# unicycle_v2_3.net
KiCad netlist of a schematic drawn in EAGLE
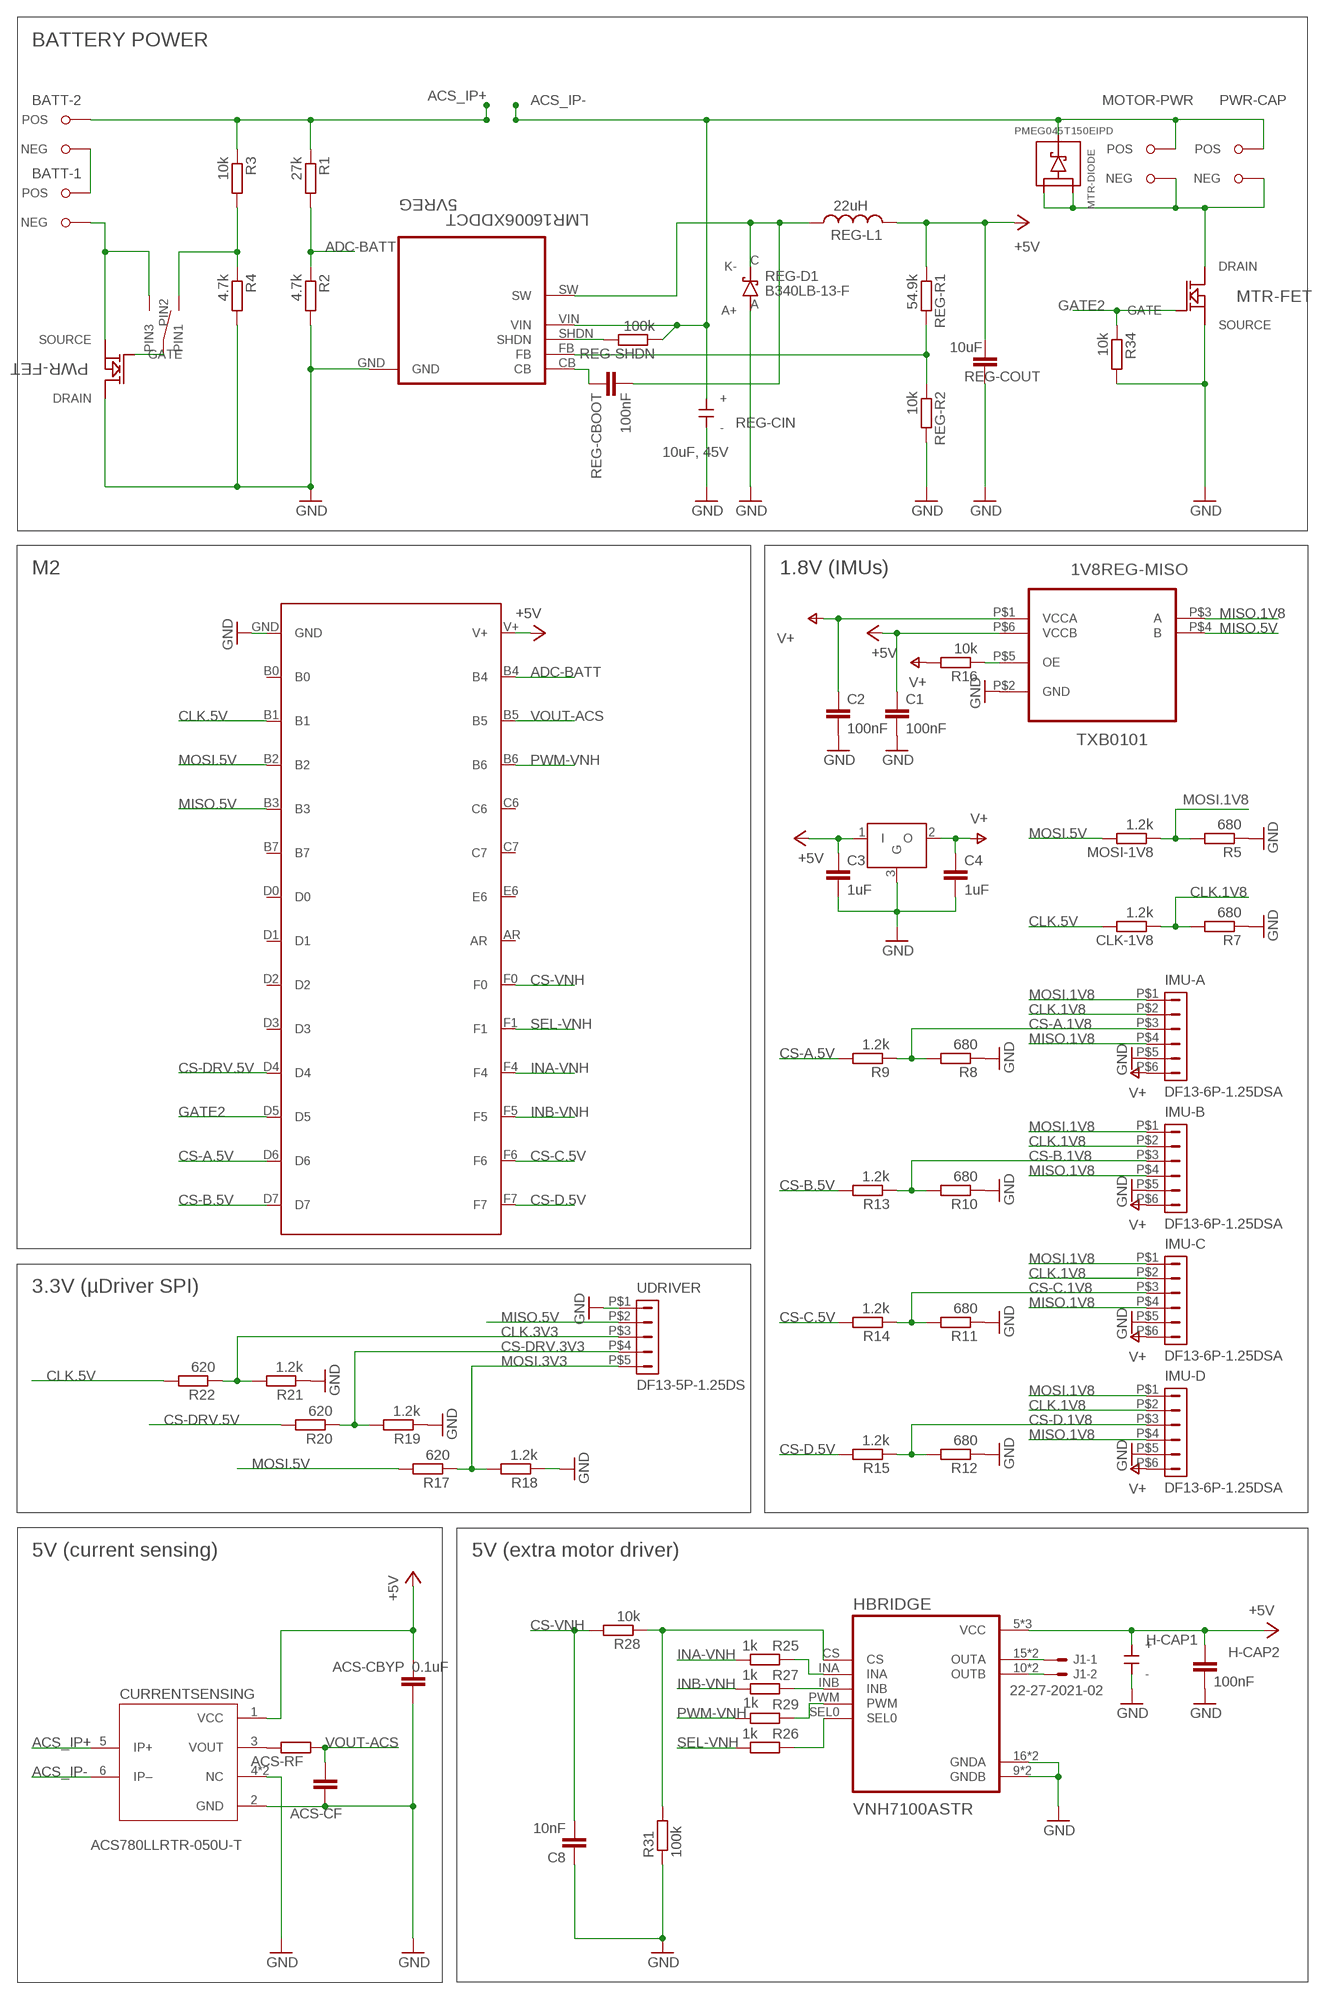
[diagram p0: schematic, sheet 1]

(export (version "E")
  (design (tool "Eeschema 10.0.6"))
  (components
    (comp (ref "1V8-REG")
      (value "AP7333AG")
      (footprint "eagle-import:SOT23")
      (libsource (lib "eagle-import") (part "AP7333AG"))
    )
    (comp (ref "1V8REG-MISO")
      (value "TXB0101")
      (footprint "eagle-import:SOT23-6")
      (libsource (lib "eagle-import") (part "TXB0101"))
    )
    (comp (ref "5VREG")
      (value "LMR16006XDDCT")
      (footprint "eagle-import:SOT95P280X110-6N")
      (fields (field (name "MF") "Texas Instruments"))
      (libsource (lib "eagle-import") (part "LMR16006XDDCT"))
    )
    (comp (ref "ACS-CBYP")
      (value "0.1uF")
      (footprint "eagle-import:C0603")
      (libsource (lib "eagle-import") (part "C-EUC0603"))
    )
    (comp (ref "ACS-CF")
      (value "C-EUC0603")
      (footprint "eagle-import:C0603")
      (libsource (lib "eagle-import") (part "C-EUC0603"))
    )
    (comp (ref "ACS-RF")
      (value "R-EU_R0603")
      (footprint "eagle-import:R0603")
      (libsource (lib "eagle-import") (part "R-EU_R0603"))
    )
    (comp (ref "C1")
      (value "100nF")
      (footprint "eagle-import:C0402")
      (libsource (lib "eagle-import") (part "zz-jpf_C-EUC0402"))
    )
    (comp (ref "C2")
      (value "100nF")
      (footprint "eagle-import:C0402")
      (libsource (lib "eagle-import") (part "zz-jpf_C-EUC0402"))
    )
    (comp (ref "C3")
      (value "1uF")
      (footprint "eagle-import:C0402")
      (libsource (lib "eagle-import") (part "zz-jpf_C-EUC0402"))
    )
    (comp (ref "C4")
      (value "1uF")
      (footprint "eagle-import:C0402")
      (libsource (lib "eagle-import") (part "zz-jpf_C-EUC0402"))
    )
    (comp (ref "C8")
      (value "10nF")
      (footprint "eagle-import:C0402")
      (libsource (lib "eagle-import") (part "zz-jpf_C-EUC0402"))
    )
    (comp (ref "CLK-1V8")
      (value "1.2k")
      (footprint "eagle-import:R0402")
      (libsource (lib "eagle-import") (part "zz-jpf_R-EU_R0402"))
    )
    (comp (ref "CURRENTSENSING")
      (value "ACS780LLRTR-050U-T")
      (footprint "eagle-import:XDCR_ACS780LLRTR-050B-T")
      (fields (field (name "MF") "Allegro MicroSystems LLC"))
      (libsource (lib "eagle-import") (part "ACS780LLRTR-050U-T"))
    )
    (comp (ref "H-CAP1")
      (value "TPSD337K006R0045")
      (footprint "eagle-import:AVX_TPS-D")
      (fields (field (name "MF") "AVX Corporation"))
      (libsource (lib "eagle-import") (part "TPSD337K006R0045"))
    )
    (comp (ref "H-CAP2")
      (value "100nF")
      (footprint "eagle-import:C0402")
      (libsource (lib "eagle-import") (part "zz-jpf_C-EUC0402"))
    )
    (comp (ref "HBRIDGE")
      (value "VNH7100ASTR")
      (footprint "eagle-import:SOIC127P600X175-16N")
      (fields (field (name "MF") "STMicroelectronics"))
      (libsource (lib "eagle-import") (part "VNH7100ASTR"))
    )
    (comp (ref "IMU-A")
      (value "DF13-6P-1.25DSA")
      (footprint "eagle-import:DF13-6P-1.25DSA")
      (libsource (lib "eagle-import") (part "DF13-6P-1.25DSA"))
    )
    (comp (ref "IMU-B")
      (value "DF13-6P-1.25DSA")
      (footprint "eagle-import:DF13-6P-1.25DSA")
      (libsource (lib "eagle-import") (part "DF13-6P-1.25DSA"))
    )
    (comp (ref "IMU-C")
      (value "DF13-6P-1.25DSA")
      (footprint "eagle-import:DF13-6P-1.25DSA")
      (libsource (lib "eagle-import") (part "DF13-6P-1.25DSA"))
    )
    (comp (ref "IMU-D")
      (value "DF13-6P-1.25DSA")
      (footprint "eagle-import:DF13-6P-1.25DSA")
      (libsource (lib "eagle-import") (part "DF13-6P-1.25DSA"))
    )
    (comp (ref "J1")
      (value "22-27-2021-02")
      (footprint "eagle-import:6410-02")
      (fields (field (name "MF") "MOLEX"))
      (libsource (lib "eagle-import") (part "22-?-0227-2021"))
    )
    (comp (ref "MOSI-1V8")
      (value "1.2k")
      (footprint "eagle-import:R0402")
      (libsource (lib "eagle-import") (part "zz-jpf_R-EU_R0402"))
    )
    (comp (ref "MOTOR-PWR")
      (value "21AWG_X2")
      (footprint "eagle-import:21AWG_X2")
      (libsource (lib "eagle-import") (part "21AWG_X2"))
    )
    (comp (ref "MTR-DIODE")
      (value "PMEG045T150EIPD")
      (footprint "eagle-import:PMEG045T150EIPD")
      (fields (field (name "MF") "Nexperia USA Inc."))
      (libsource (lib "eagle-import") (part "PMEG045T150EIPD"))
    )
    (comp (ref "MTR-FET")
      (value "CSD18540Q5BT")
      (footprint "eagle-import:DNK0008A")
      (fields (field (name "MF") "Texas Instruments"))
      (libsource (lib "eagle-import") (part "CSD18540Q5BT"))
    )
    (comp (ref "PWR-CAP")
      (value "21AWG_X2")
      (footprint "eagle-import:21AWG_X2")
      (libsource (lib "eagle-import") (part "21AWG_X2"))
    )
    (comp (ref "PWR-FET")
      (value "CSD18540Q5BT")
      (footprint "eagle-import:DNK0008A")
      (fields (field (name "MF") "Texas Instruments"))
      (libsource (lib "eagle-import") (part "CSD18540Q5BT"))
    )
    (comp (ref "R1")
      (value "27k")
      (footprint "eagle-import:R0402")
      (libsource (lib "eagle-import") (part "zz-jpf_R-EU_R0402"))
    )
    (comp (ref "R2")
      (value "4.7k")
      (footprint "eagle-import:R0402")
      (libsource (lib "eagle-import") (part "zz-jpf_R-EU_R0402"))
    )
    (comp (ref "R3")
      (value "10k")
      (footprint "eagle-import:R0402")
      (libsource (lib "eagle-import") (part "zz-jpf_R-EU_R0402"))
    )
    (comp (ref "R4")
      (value "4.7k")
      (footprint "eagle-import:R0402")
      (libsource (lib "eagle-import") (part "zz-jpf_R-EU_R0402"))
    )
    (comp (ref "R5")
      (value "680")
      (footprint "eagle-import:R0402")
      (libsource (lib "eagle-import") (part "zz-jpf_R-EU_R0402"))
    )
    (comp (ref "R7")
      (value "680")
      (footprint "eagle-import:R0402")
      (libsource (lib "eagle-import") (part "zz-jpf_R-EU_R0402"))
    )
    (comp (ref "R8")
      (value "680")
      (footprint "eagle-import:R0402")
      (libsource (lib "eagle-import") (part "zz-jpf_R-EU_R0402"))
    )
    (comp (ref "R9")
      (value "1.2k")
      (footprint "eagle-import:R0402")
      (libsource (lib "eagle-import") (part "zz-jpf_R-EU_R0402"))
    )
    (comp (ref "R10")
      (value "680")
      (footprint "eagle-import:R0402")
      (libsource (lib "eagle-import") (part "zz-jpf_R-EU_R0402"))
    )
    (comp (ref "R11")
      (value "680")
      (footprint "eagle-import:R0402")
      (libsource (lib "eagle-import") (part "zz-jpf_R-EU_R0402"))
    )
    (comp (ref "R12")
      (value "680")
      (footprint "eagle-import:R0402")
      (libsource (lib "eagle-import") (part "zz-jpf_R-EU_R0402"))
    )
    (comp (ref "R13")
      (value "1.2k")
      (footprint "eagle-import:R0402")
      (libsource (lib "eagle-import") (part "zz-jpf_R-EU_R0402"))
    )
    (comp (ref "R14")
      (value "1.2k")
      (footprint "eagle-import:R0402")
      (libsource (lib "eagle-import") (part "zz-jpf_R-EU_R0402"))
    )
    (comp (ref "R15")
      (value "1.2k")
      (footprint "eagle-import:R0402")
      (libsource (lib "eagle-import") (part "zz-jpf_R-EU_R0402"))
    )
    (comp (ref "R16")
      (value "10k")
      (footprint "eagle-import:R0402")
      (libsource (lib "eagle-import") (part "zz-jpf_R-EU_R0402"))
    )
    (comp (ref "R17")
      (value "620")
      (footprint "eagle-import:R0402")
      (libsource (lib "eagle-import") (part "zz-jpf_R-EU_R0402"))
    )
    (comp (ref "R18")
      (value "1.2k")
      (footprint "eagle-import:R0402")
      (libsource (lib "eagle-import") (part "zz-jpf_R-EU_R0402"))
    )
    (comp (ref "R19")
      (value "1.2k")
      (footprint "eagle-import:R0402")
      (libsource (lib "eagle-import") (part "zz-jpf_R-EU_R0402"))
    )
    (comp (ref "R20")
      (value "620")
      (footprint "eagle-import:R0402")
      (libsource (lib "eagle-import") (part "zz-jpf_R-EU_R0402"))
    )
    (comp (ref "R21")
      (value "1.2k")
      (footprint "eagle-import:R0402")
      (libsource (lib "eagle-import") (part "zz-jpf_R-EU_R0402"))
    )
    (comp (ref "R22")
      (value "620")
      (footprint "eagle-import:R0402")
      (libsource (lib "eagle-import") (part "zz-jpf_R-EU_R0402"))
    )
    (comp (ref "R25")
      (value "1k")
      (footprint "eagle-import:R0402")
      (libsource (lib "eagle-import") (part "zz-jpf_R-EU_R0402"))
    )
    (comp (ref "R26")
      (value "1k")
      (footprint "eagle-import:R0402")
      (libsource (lib "eagle-import") (part "zz-jpf_R-EU_R0402"))
    )
    (comp (ref "R27")
      (value "1k")
      (footprint "eagle-import:R0402")
      (libsource (lib "eagle-import") (part "zz-jpf_R-EU_R0402"))
    )
    (comp (ref "R28")
      (value "10k")
      (footprint "eagle-import:R0402")
      (libsource (lib "eagle-import") (part "zz-jpf_R-EU_R0402"))
    )
    (comp (ref "R29")
      (value "1k")
      (footprint "eagle-import:R0402")
      (libsource (lib "eagle-import") (part "zz-jpf_R-EU_R0402"))
    )
    (comp (ref "R31")
      (value "100k")
      (footprint "eagle-import:R0402")
      (libsource (lib "eagle-import") (part "zz-jpf_R-EU_R0402"))
    )
    (comp (ref "R34")
      (value "10k")
      (footprint "eagle-import:R0402")
      (libsource (lib "eagle-import") (part "zz-jpf_R-EU_R0402"))
    )
    (comp (ref "REG-CBOOT")
      (value "100nF")
      (footprint "eagle-import:C0402")
      (libsource (lib "eagle-import") (part "zz-jpf_C-EUC0402"))
    )
    (comp (ref "REG-CIN")
      (value "10uF, 45V")
      (footprint "eagle-import:TCJD106M050R0120")
      (fields (field (name "MF") "AVX"))
      (libsource (lib "eagle-import") (part "TCJD106M050R0120"))
    )
    (comp (ref "REG-COUT")
      (value "10uF")
      (footprint "eagle-import:C0603")
      (libsource (lib "eagle-import") (part "zz-jpf_C-EUC0603"))
    )
    (comp (ref "REG-D1")
      (value "B340LB-13-F")
      (footprint "eagle-import:DIODES-SMB")
      (fields (field (name "MF") "DiodesZetex"))
      (libsource (lib "eagle-import") (part "B340LB-13-F"))
    )
    (comp (ref "REG-L1")
      (value "22uH")
      (footprint "eagle-import:4020")
      (fields (field (name "MF") "Wurth Elektronik"))
      (libsource (lib "eagle-import") (part "IND-LHMI"))
    )
    (comp (ref "REG-R1")
      (value "54.9k")
      (footprint "eagle-import:R0402")
      (libsource (lib "eagle-import") (part "zz-jpf_R-EU_R0402"))
    )
    (comp (ref "REG-R2")
      (value "10k")
      (footprint "eagle-import:R0402")
      (libsource (lib "eagle-import") (part "zz-jpf_R-EU_R0402"))
    )
    (comp (ref "REG-SHDN")
      (value "100k")
      (footprint "eagle-import:R0402")
      (libsource (lib "eagle-import") (part "zz-jpf_R-EU_R0402"))
    )
    (comp (ref "SWITCH")
      (value "ATE1D-2M3-10-Z")
      (footprint "eagle-import:ATE1D-2M3-10-Z")
      (fields (field (name "MF") "nidec copal electronics"))
      (libsource (lib "eagle-import") (part "ATE1D-2M3-10-Z"))
    )
    (comp (ref "U$2") (value "M2") (footprint "eagle-import:M1") (libsource (lib "eagle-import") (part "M2")))
    (comp (ref "U$8")
      (value "XT30PW-M")
      (footprint "eagle-import:XT30PW-M-NOHOLE")
      (libsource (lib "eagle-import") (part "XT30PW-M"))
    )
    (comp (ref "U$9")
      (value "XT30PW-M")
      (footprint "eagle-import:XT30PW-M-NOHOLE")
      (libsource (lib "eagle-import") (part "XT30PW-M"))
    )
    (comp (ref "UDRIVER")
      (value "DF13-5P-1.25DS")
      (footprint "eagle-import:DF13-5P-1.25DS")
      (libsource (lib "eagle-import") (part "DF13-5P-1.25DS"))
    )
  )
  (nets
    (net (code "1") (name "+5V") (class "Default")
      (node (ref "1V8-REG") (pin "1") (pinfunction "I_1") (pintype "bidirectional"))
      (node (ref "1V8REG-MISO") (pin "P$6") (pinfunction "VCCB_P$6") (pintype "power_in"))
      (node (ref "ACS-CBYP") (pin "2") (pinfunction "2_2") (pintype "passive"))
      (node (ref "C1") (pin "1") (pinfunction "1_1") (pintype "passive"))
      (node (ref "C3") (pin "1") (pinfunction "1_1") (pintype "passive"))
      (node (ref "CURRENTSENSING") (pin "1") (pinfunction "VCC_1") (pintype "power_in"))
      (node (ref "H-CAP1") (pin "POS") (pinfunction "+_POS") (pintype "passive"))
      (node (ref "H-CAP2") (pin "1") (pinfunction "1_1") (pintype "passive"))
      (node (ref "HBRIDGE") (pin "12") (pinfunction "VCC_12") (pintype "power_in"))
      (node (ref "HBRIDGE") (pin "5") (pinfunction "VCC_5") (pintype "power_in"))
      (node (ref "HBRIDGE") (pin "VCC") (pinfunction "VCC_VCC") (pintype "power_in"))
      (node (ref "REG-COUT") (pin "1") (pinfunction "1_1") (pintype "passive"))
      (node (ref "REG-L1") (pin "P$2") (pinfunction "2_P$2") (pintype "passive"))
      (node (ref "REG-R1") (pin "1") (pinfunction "1_1") (pintype "passive"))
      (node (ref "U$2") (pin "V+") (pinfunction "V+_V+") (pintype "bidirectional"))
    )
    (net (code "2") (name "/ACS_IP+") (class "Default")
      (node (ref "CURRENTSENSING") (pin "5") (pinfunction "IP+_5") (pintype "input"))
      (node (ref "R1") (pin "1") (pinfunction "1_1") (pintype "passive"))
      (node (ref "R3") (pin "1") (pinfunction "1_1") (pintype "passive"))
      (node (ref "U$8") (pin "POS") (pinfunction "POS_POS") (pintype "bidirectional"))
    )
    (net (code "3") (name "/ACS_IP-") (class "Default")
      (node (ref "5VREG") (pin "VIN") (pinfunction "VIN_VIN") (pintype "input"))
      (node (ref "CURRENTSENSING") (pin "6") (pinfunction "IP–_6") (pintype "input"))
      (node (ref "MOTOR-PWR") (pin "POS") (pinfunction "POS_POS") (pintype "bidirectional"))
      (node (ref "MTR-DIODE") (pin "3") (pinfunction "K_3") (pintype "bidirectional"))
      (node (ref "PWR-CAP") (pin "POS") (pinfunction "POS_POS") (pintype "bidirectional"))
      (node (ref "REG-CIN") (pin "POS") (pinfunction "+_POS") (pintype "passive"))
      (node (ref "REG-SHDN") (pin "1") (pinfunction "1_1") (pintype "passive"))
    )
    (net (code "4") (name "/ADC-BATT") (class "Default")
      (node (ref "R1") (pin "2") (pinfunction "2_2") (pintype "passive"))
      (node (ref "R2") (pin "1") (pinfunction "1_1") (pintype "passive"))
      (node (ref "U$2") (pin "B4") (pinfunction "B4_B4") (pintype "bidirectional"))
    )
    (net (code "5") (name "/CLK.1V8") (class "Default")
      (node (ref "CLK-1V8") (pin "1") (pinfunction "1_1") (pintype "passive"))
      (node (ref "IMU-A") (pin "P$2") (pinfunction "2_P$2") (pintype "passive"))
      (node (ref "IMU-B") (pin "P$2") (pinfunction "2_P$2") (pintype "passive"))
      (node (ref "IMU-C") (pin "P$2") (pinfunction "2_P$2") (pintype "passive"))
      (node (ref "IMU-D") (pin "P$2") (pinfunction "2_P$2") (pintype "passive"))
      (node (ref "R7") (pin "2") (pinfunction "2_2") (pintype "passive"))
    )
    (net (code "6") (name "/CLK.3V3") (class "Default")
      (node (ref "R21") (pin "2") (pinfunction "2_2") (pintype "passive"))
      (node (ref "R22") (pin "1") (pinfunction "1_1") (pintype "passive"))
      (node (ref "UDRIVER") (pin "P$3") (pinfunction "3_P$3") (pintype "passive"))
    )
    (net (code "7") (name "/CLK.5V") (class "Default")
      (node (ref "CLK-1V8") (pin "2") (pinfunction "2_2") (pintype "passive"))
      (node (ref "R22") (pin "2") (pinfunction "2_2") (pintype "passive"))
      (node (ref "U$2") (pin "B1") (pinfunction "B1_B1") (pintype "bidirectional"))
    )
    (net (code "8") (name "/CS-A.1V8") (class "Default")
      (node (ref "IMU-A") (pin "P$3") (pinfunction "3_P$3") (pintype "passive"))
      (node (ref "R8") (pin "2") (pinfunction "2_2") (pintype "passive"))
      (node (ref "R9") (pin "1") (pinfunction "1_1") (pintype "passive"))
    )
    (net (code "9") (name "/CS-A.5V") (class "Default")
      (node (ref "R9") (pin "2") (pinfunction "2_2") (pintype "passive"))
      (node (ref "U$2") (pin "D6") (pinfunction "D6_D6") (pintype "bidirectional"))
    )
    (net (code "10") (name "/CS-B.1V8") (class "Default")
      (node (ref "IMU-B") (pin "P$3") (pinfunction "3_P$3") (pintype "passive"))
      (node (ref "R10") (pin "2") (pinfunction "2_2") (pintype "passive"))
      (node (ref "R13") (pin "1") (pinfunction "1_1") (pintype "passive"))
    )
    (net (code "11") (name "/CS-B.5V") (class "Default")
      (node (ref "R13") (pin "2") (pinfunction "2_2") (pintype "passive"))
      (node (ref "U$2") (pin "D7") (pinfunction "D7_D7") (pintype "bidirectional"))
    )
    (net (code "12") (name "/CS-C.1V8") (class "Default")
      (node (ref "IMU-C") (pin "P$3") (pinfunction "3_P$3") (pintype "passive"))
      (node (ref "R11") (pin "2") (pinfunction "2_2") (pintype "passive"))
      (node (ref "R14") (pin "1") (pinfunction "1_1") (pintype "passive"))
    )
    (net (code "13") (name "/CS-C.5V") (class "Default")
      (node (ref "R14") (pin "2") (pinfunction "2_2") (pintype "passive"))
      (node (ref "U$2") (pin "F6") (pinfunction "F6_F6") (pintype "bidirectional"))
    )
    (net (code "14") (name "/CS-D.1V8") (class "Default")
      (node (ref "IMU-D") (pin "P$3") (pinfunction "3_P$3") (pintype "passive"))
      (node (ref "R12") (pin "2") (pinfunction "2_2") (pintype "passive"))
      (node (ref "R15") (pin "1") (pinfunction "1_1") (pintype "passive"))
    )
    (net (code "15") (name "/CS-D.5V") (class "Default")
      (node (ref "R15") (pin "2") (pinfunction "2_2") (pintype "passive"))
      (node (ref "U$2") (pin "F7") (pinfunction "F7_F7") (pintype "bidirectional"))
    )
    (net (code "16") (name "/CS-DRV.3V3") (class "Default")
      (node (ref "R19") (pin "2") (pinfunction "2_2") (pintype "passive"))
      (node (ref "R20") (pin "1") (pinfunction "1_1") (pintype "passive"))
      (node (ref "UDRIVER") (pin "P$4") (pinfunction "4_P$4") (pintype "passive"))
    )
    (net (code "17") (name "/CS-DRV.5V") (class "Default")
      (node (ref "R20") (pin "2") (pinfunction "2_2") (pintype "passive"))
      (node (ref "U$2") (pin "D4") (pinfunction "D4_D4") (pintype "bidirectional"))
    )
    (net (code "18") (name "/CS-VNH") (class "Default")
      (node (ref "C8") (pin "2") (pinfunction "2_2") (pintype "passive"))
      (node (ref "R28") (pin "2") (pinfunction "2_2") (pintype "passive"))
      (node (ref "U$2") (pin "F0") (pinfunction "F0_F0") (pintype "bidirectional"))
    )
    (net (code "19") (name "/GATE2") (class "Default")
      (node (ref "MTR-FET") (pin "4") (pinfunction "GATE_4") (pintype "passive"))
      (node (ref "R34") (pin "1") (pinfunction "1_1") (pintype "passive"))
      (node (ref "U$2") (pin "D5") (pinfunction "D5_D5") (pintype "bidirectional"))
    )
    (net (code "20") (name "/INA-VNH") (class "Default")
      (node (ref "R25") (pin "2") (pinfunction "2_2") (pintype "passive"))
      (node (ref "U$2") (pin "F4") (pinfunction "F4_F4") (pintype "bidirectional"))
    )
    (net (code "21") (name "/INB-VNH") (class "Default")
      (node (ref "R27") (pin "2") (pinfunction "2_2") (pintype "passive"))
      (node (ref "U$2") (pin "F5") (pinfunction "F5_F5") (pintype "bidirectional"))
    )
    (net (code "22") (name "/MISO.1V8") (class "Default")
      (node (ref "1V8REG-MISO") (pin "P$3") (pinfunction "A_P$3") (pintype "bidirectional"))
      (node (ref "IMU-A") (pin "P$4") (pinfunction "4_P$4") (pintype "passive"))
      (node (ref "IMU-B") (pin "P$4") (pinfunction "4_P$4") (pintype "passive"))
      (node (ref "IMU-C") (pin "P$4") (pinfunction "4_P$4") (pintype "passive"))
      (node (ref "IMU-D") (pin "P$4") (pinfunction "4_P$4") (pintype "passive"))
    )
    (net (code "23") (name "/MISO.5V") (class "Default")
      (node (ref "1V8REG-MISO") (pin "P$4") (pinfunction "B_P$4") (pintype "bidirectional"))
      (node (ref "U$2") (pin "B3") (pinfunction "B3_B3") (pintype "bidirectional"))
      (node (ref "UDRIVER") (pin "P$2") (pinfunction "2_P$2") (pintype "passive"))
    )
    (net (code "24") (name "/MOSI.1V8") (class "Default")
      (node (ref "IMU-A") (pin "P$1") (pinfunction "1_P$1") (pintype "passive"))
      (node (ref "IMU-B") (pin "P$1") (pinfunction "1_P$1") (pintype "passive"))
      (node (ref "IMU-C") (pin "P$1") (pinfunction "1_P$1") (pintype "passive"))
      (node (ref "IMU-D") (pin "P$1") (pinfunction "1_P$1") (pintype "passive"))
      (node (ref "MOSI-1V8") (pin "1") (pinfunction "1_1") (pintype "passive"))
      (node (ref "R5") (pin "2") (pinfunction "2_2") (pintype "passive"))
    )
    (net (code "25") (name "/MOSI.3V3") (class "Default")
      (node (ref "R17") (pin "1") (pinfunction "1_1") (pintype "passive"))
      (node (ref "R18") (pin "2") (pinfunction "2_2") (pintype "passive"))
      (node (ref "UDRIVER") (pin "P$5") (pinfunction "5_P$5") (pintype "passive"))
    )
    (net (code "26") (name "/MOSI.5V") (class "Default")
      (node (ref "MOSI-1V8") (pin "2") (pinfunction "2_2") (pintype "passive"))
      (node (ref "R17") (pin "2") (pinfunction "2_2") (pintype "passive"))
      (node (ref "U$2") (pin "B2") (pinfunction "B2_B2") (pintype "bidirectional"))
    )
    (net (code "27") (name "/PWM-VNH") (class "Default")
      (node (ref "R29") (pin "2") (pinfunction "2_2") (pintype "passive"))
      (node (ref "U$2") (pin "B6") (pinfunction "B6_B6") (pintype "bidirectional"))
    )
    (net (code "28") (name "/SEL-VNH") (class "Default")
      (node (ref "R26") (pin "2") (pinfunction "2_2") (pintype "passive"))
      (node (ref "U$2") (pin "F1") (pinfunction "F1_F1") (pintype "bidirectional"))
    )
    (net (code "29") (name "/VOUT-ACS") (class "Default")
      (node (ref "ACS-CF") (pin "1") (pinfunction "1_1") (pintype "passive"))
      (node (ref "ACS-RF") (pin "1") (pinfunction "1_1") (pintype "passive"))
      (node (ref "U$2") (pin "B5") (pinfunction "B5_B5") (pintype "bidirectional"))
    )
    (net (code "30") (name "GND") (class "Default")
      (node (ref "1V8-REG") (pin "3") (pinfunction "G_3") (pintype "bidirectional"))
      (node (ref "1V8REG-MISO") (pin "P$2") (pinfunction "GND_P$2") (pintype "passive"))
      (node (ref "5VREG") (pin "GND") (pinfunction "GND_GND") (pintype "power_in"))
      (node (ref "ACS-CBYP") (pin "1") (pinfunction "1_1") (pintype "passive"))
      (node (ref "ACS-CF") (pin "2") (pinfunction "2_2") (pintype "passive"))
      (node (ref "C1") (pin "2") (pinfunction "2_2") (pintype "passive"))
      (node (ref "C2") (pin "2") (pinfunction "2_2") (pintype "passive"))
      (node (ref "C3") (pin "2") (pinfunction "2_2") (pintype "passive"))
      (node (ref "C4") (pin "2") (pinfunction "2_2") (pintype "passive"))
      (node (ref "C8") (pin "1") (pinfunction "1_1") (pintype "passive"))
      (node (ref "CURRENTSENSING") (pin "2") (pinfunction "GND_2") (pintype "power_in"))
      (node (ref "CURRENTSENSING") (pin "4") (pinfunction "NC_4") (pintype "passive"))
      (node (ref "CURRENTSENSING") (pin "7") (pinfunction "NC_7") (pintype "passive"))
      (node (ref "H-CAP1") (pin "NEG") (pinfunction "-_NEG") (pintype "passive"))
      (node (ref "H-CAP2") (pin "2") (pinfunction "2_2") (pintype "passive"))
      (node (ref "HBRIDGE") (pin "16") (pinfunction "GNDA_16") (pintype "power_in"))
      (node (ref "HBRIDGE") (pin "9") (pinfunction "GNDB_9") (pintype "power_in"))
      (node (ref "HBRIDGE") (pin "GNDA") (pinfunction "GNDA_GNDA") (pintype "power_in"))
      (node (ref "HBRIDGE") (pin "GNDB") (pinfunction "GNDB_GNDB") (pintype "power_in"))
      (node (ref "IMU-A") (pin "P$5") (pinfunction "5_P$5") (pintype "passive"))
      (node (ref "IMU-B") (pin "P$5") (pinfunction "5_P$5") (pintype "passive"))
      (node (ref "IMU-C") (pin "P$5") (pinfunction "5_P$5") (pintype "passive"))
      (node (ref "IMU-D") (pin "P$5") (pinfunction "5_P$5") (pintype "passive"))
      (node (ref "MTR-FET") (pin "1") (pinfunction "SOURCE_1") (pintype "passive"))
      (node (ref "MTR-FET") (pin "2") (pinfunction "SOURCE_2") (pintype "passive"))
      (node (ref "MTR-FET") (pin "3") (pinfunction "SOURCE_3") (pintype "passive"))
      (node (ref "PWR-FET") (pin "9") (pinfunction "DRAIN_9") (pintype "passive"))
      (node (ref "R10") (pin "1") (pinfunction "1_1") (pintype "passive"))
      (node (ref "R11") (pin "1") (pinfunction "1_1") (pintype "passive"))
      (node (ref "R12") (pin "1") (pinfunction "1_1") (pintype "passive"))
      (node (ref "R18") (pin "1") (pinfunction "1_1") (pintype "passive"))
      (node (ref "R19") (pin "1") (pinfunction "1_1") (pintype "passive"))
      (node (ref "R2") (pin "2") (pinfunction "2_2") (pintype "passive"))
      (node (ref "R21") (pin "1") (pinfunction "1_1") (pintype "passive"))
      (node (ref "R31") (pin "1") (pinfunction "1_1") (pintype "passive"))
      (node (ref "R34") (pin "2") (pinfunction "2_2") (pintype "passive"))
      (node (ref "R4") (pin "2") (pinfunction "2_2") (pintype "passive"))
      (node (ref "R5") (pin "1") (pinfunction "1_1") (pintype "passive"))
      (node (ref "R7") (pin "1") (pinfunction "1_1") (pintype "passive"))
      (node (ref "R8") (pin "1") (pinfunction "1_1") (pintype "passive"))
      (node (ref "REG-CIN") (pin "NEG") (pinfunction "-_NEG") (pintype "passive"))
      (node (ref "REG-COUT") (pin "2") (pinfunction "2_2") (pintype "passive"))
      (node (ref "REG-D1") (pin "A") (pinfunction "A+_A") (pintype "bidirectional"))
      (node (ref "REG-R2") (pin "2") (pinfunction "2_2") (pintype "passive"))
      (node (ref "U$2") (pin "GND") (pinfunction "GND_GND") (pintype "bidirectional"))
      (node (ref "UDRIVER") (pin "P$1") (pinfunction "1_P$1") (pintype "passive"))
    )
    (net (code "31") (name "Net-(1V8REG-MISO-OE)") (class "Default")
      (node (ref "1V8REG-MISO") (pin "P$5") (pinfunction "OE_P$5") (pintype "input"))
      (node (ref "R16") (pin "1") (pinfunction "1_1") (pintype "passive"))
    )
    (net (code "32") (name "Net-(5VREG-PadCB)") (class "Default")
      (node (ref "5VREG") (pin "CB") (pinfunction "CB_CB") (pintype "input"))
      (node (ref "REG-CBOOT") (pin "2") (pinfunction "2_2") (pintype "passive"))
    )
    (net (code "33") (name "Net-(5VREG-PadFB)") (class "Default")
      (node (ref "5VREG") (pin "FB") (pinfunction "FB_FB") (pintype "input"))
      (node (ref "REG-R1") (pin "2") (pinfunction "2_2") (pintype "passive"))
      (node (ref "REG-R2") (pin "1") (pinfunction "1_1") (pintype "passive"))
    )
    (net (code "34") (name "Net-(5VREG-PadSHDN)") (class "Default")
      (node (ref "5VREG") (pin "SHDN") (pinfunction "SHDN_SHDN") (pintype "input"))
      (node (ref "REG-SHDN") (pin "2") (pinfunction "2_2") (pintype "passive"))
    )
    (net (code "35") (name "Net-(CURRENTSENSING-VOUT)") (class "Default")
      (node (ref "ACS-RF") (pin "2") (pinfunction "2_2") (pintype "passive"))
      (node (ref "CURRENTSENSING") (pin "3") (pinfunction "VOUT_3") (pintype "output"))
    )
    (net (code "36") (name "Net-(HBRIDGE-PadCS)") (class "Default")
      (node (ref "HBRIDGE") (pin "CS") (pinfunction "CS_CS") (pintype "input"))
      (node (ref "R28") (pin "1") (pinfunction "1_1") (pintype "passive"))
      (node (ref "R31") (pin "2") (pinfunction "2_2") (pintype "passive"))
    )
    (net (code "37") (name "Net-(HBRIDGE-PadINA)") (class "Default")
      (node (ref "HBRIDGE") (pin "INA") (pinfunction "INA_INA") (pintype "input"))
      (node (ref "R25") (pin "1") (pinfunction "1_1") (pintype "passive"))
    )
    (net (code "38") (name "Net-(HBRIDGE-PadINB)") (class "Default")
      (node (ref "HBRIDGE") (pin "INB") (pinfunction "INB_INB") (pintype "input"))
      (node (ref "R27") (pin "1") (pinfunction "1_1") (pintype "passive"))
    )
    (net (code "39") (name "Net-(HBRIDGE-PadPWM)") (class "Default")
      (node (ref "HBRIDGE") (pin "PWM") (pinfunction "PWM_PWM") (pintype "input"))
      (node (ref "R29") (pin "1") (pinfunction "1_1") (pintype "passive"))
    )
    (net (code "40") (name "Net-(HBRIDGE-PadSEL0)") (class "Default")
      (node (ref "HBRIDGE") (pin "SEL0") (pinfunction "SEL0_SEL0") (pintype "input"))
      (node (ref "R26") (pin "1") (pinfunction "1_1") (pintype "passive"))
    )
    (net (code "41") (name "Net-(J1A-S)") (class "Default")
      (node (ref "HBRIDGE") (pin "15") (pinfunction "OUTA_15") (pintype "output"))
      (node (ref "HBRIDGE") (pin "OUTA") (pinfunction "OUTA_OUTA") (pintype "output"))
      (node (ref "J1") (pin "1") (pinfunction "S_1") (pintype "passive"))
    )
    (net (code "42") (name "Net-(J1B-S)") (class "Default")
      (node (ref "HBRIDGE") (pin "10") (pinfunction "OUTB_10") (pintype "output"))
      (node (ref "HBRIDGE") (pin "OUTB") (pinfunction "OUTB_OUTB") (pintype "output"))
      (node (ref "J1") (pin "2") (pinfunction "S_2") (pintype "passive"))
    )
    (net (code "43") (name "Net-(MTR-DIODE-A1)") (class "Default")
      (node (ref "MOTOR-PWR") (pin "NEG") (pinfunction "NEG_NEG") (pintype "bidirectional"))
      (node (ref "MTR-DIODE") (pin "1") (pinfunction "A1_1") (pintype "bidirectional"))
      (node (ref "MTR-DIODE") (pin "2") (pinfunction "A2_2") (pintype "bidirectional"))
      (node (ref "MTR-FET") (pin "9") (pinfunction "DRAIN_9") (pintype "passive"))
      (node (ref "PWR-CAP") (pin "NEG") (pinfunction "NEG_NEG") (pintype "bidirectional"))
    )
    (net (code "44") (name "Net-(PWR-FET-GATE)") (class "Default")
      (node (ref "PWR-FET") (pin "4") (pinfunction "GATE_4") (pintype "passive"))
      (node (ref "SWITCH") (pin "P$2") (pinfunction "PIN2_P$2") (pintype "bidirectional"))
    )
    (net (code "45") (name "Net-(REG-D1-K-)") (class "Default")
      (node (ref "5VREG") (pin "SW") (pinfunction "SW_SW") (pintype "bidirectional"))
      (node (ref "REG-CBOOT") (pin "1") (pinfunction "1_1") (pintype "passive"))
      (node (ref "REG-D1") (pin "C") (pinfunction "K-_C") (pintype "bidirectional"))
      (node (ref "REG-L1") (pin "P$1") (pinfunction "1_P$1") (pintype "passive"))
    )
    (net (code "46") (name "Net-(SWITCH-PIN1)") (class "Default")
      (node (ref "R3") (pin "2") (pinfunction "2_2") (pintype "passive"))
      (node (ref "R4") (pin "1") (pinfunction "1_1") (pintype "passive"))
      (node (ref "SWITCH") (pin "P$1") (pinfunction "PIN1_P$1") (pintype "bidirectional"))
    )
    (net (code "47") (name "Net-(SWITCH-PIN3)") (class "Default")
      (node (ref "PWR-FET") (pin "1") (pinfunction "SOURCE_1") (pintype "passive"))
      (node (ref "PWR-FET") (pin "2") (pinfunction "SOURCE_2") (pintype "passive"))
      (node (ref "PWR-FET") (pin "3") (pinfunction "SOURCE_3") (pintype "passive"))
      (node (ref "SWITCH") (pin "P$3") (pinfunction "PIN3_P$3") (pintype "bidirectional"))
      (node (ref "U$9") (pin "NEG") (pinfunction "NEG_NEG") (pintype "bidirectional"))
    )
    (net (code "48") (name "Net-(U$8-PadNEG)") (class "Default")
      (node (ref "U$8") (pin "NEG") (pinfunction "NEG_NEG") (pintype "bidirectional"))
      (node (ref "U$9") (pin "POS") (pinfunction "POS_POS") (pintype "bidirectional"))
    )
    (net (code "49") (name "V+") (class "Default")
      (node (ref "1V8-REG") (pin "2") (pinfunction "O_2") (pintype "bidirectional"))
      (node (ref "1V8REG-MISO") (pin "P$1") (pinfunction "VCCA_P$1") (pintype "power_in"))
      (node (ref "C2") (pin "1") (pinfunction "1_1") (pintype "passive"))
      (node (ref "C4") (pin "1") (pinfunction "1_1") (pintype "passive"))
      (node (ref "IMU-A") (pin "P$6") (pinfunction "6_P$6") (pintype "passive"))
      (node (ref "IMU-B") (pin "P$6") (pinfunction "6_P$6") (pintype "passive"))
      (node (ref "IMU-C") (pin "P$6") (pinfunction "6_P$6") (pintype "passive"))
      (node (ref "IMU-D") (pin "P$6") (pinfunction "6_P$6") (pintype "passive"))
      (node (ref "R16") (pin "2") (pinfunction "2_2") (pintype "passive"))
    )
    (net (code "50") (name "unconnected-(U$2-PadAR)") (class "Default")
      (node (ref "U$2") (pin "AR") (pinfunction "AR_AR") (pintype "bidirectional"))
    )
    (net (code "51") (name "unconnected-(U$2-PadB0)") (class "Default")
      (node (ref "U$2") (pin "B0") (pinfunction "B0_B0") (pintype "bidirectional"))
    )
    (net (code "52") (name "unconnected-(U$2-PadB7)") (class "Default")
      (node (ref "U$2") (pin "B7") (pinfunction "B7_B7") (pintype "bidirectional"))
    )
    (net (code "53") (name "unconnected-(U$2-PadC6)") (class "Default")
      (node (ref "U$2") (pin "C6") (pinfunction "C6_C6") (pintype "bidirectional"))
    )
    (net (code "54") (name "unconnected-(U$2-PadC7)") (class "Default")
      (node (ref "U$2") (pin "C7") (pinfunction "C7_C7") (pintype "bidirectional"))
    )
    (net (code "55") (name "unconnected-(U$2-PadD0)") (class "Default")
      (node (ref "U$2") (pin "D0") (pinfunction "D0_D0") (pintype "bidirectional"))
    )
    (net (code "56") (name "unconnected-(U$2-PadD1)") (class "Default")
      (node (ref "U$2") (pin "D1") (pinfunction "D1_D1") (pintype "bidirectional"))
    )
    (net (code "57") (name "unconnected-(U$2-PadD2)") (class "Default")
      (node (ref "U$2") (pin "D2") (pinfunction "D2_D2") (pintype "bidirectional"))
    )
    (net (code "58") (name "unconnected-(U$2-PadD3)") (class "Default")
      (node (ref "U$2") (pin "D3") (pinfunction "D3_D3") (pintype "bidirectional"))
    )
    (net (code "59") (name "unconnected-(U$2-PadE6)") (class "Default")
      (node (ref "U$2") (pin "E6") (pinfunction "E6_E6") (pintype "bidirectional"))
    )
  )
)
